# Nusbio_smd.net
KiCad netlist of a schematic drawn in EAGLE
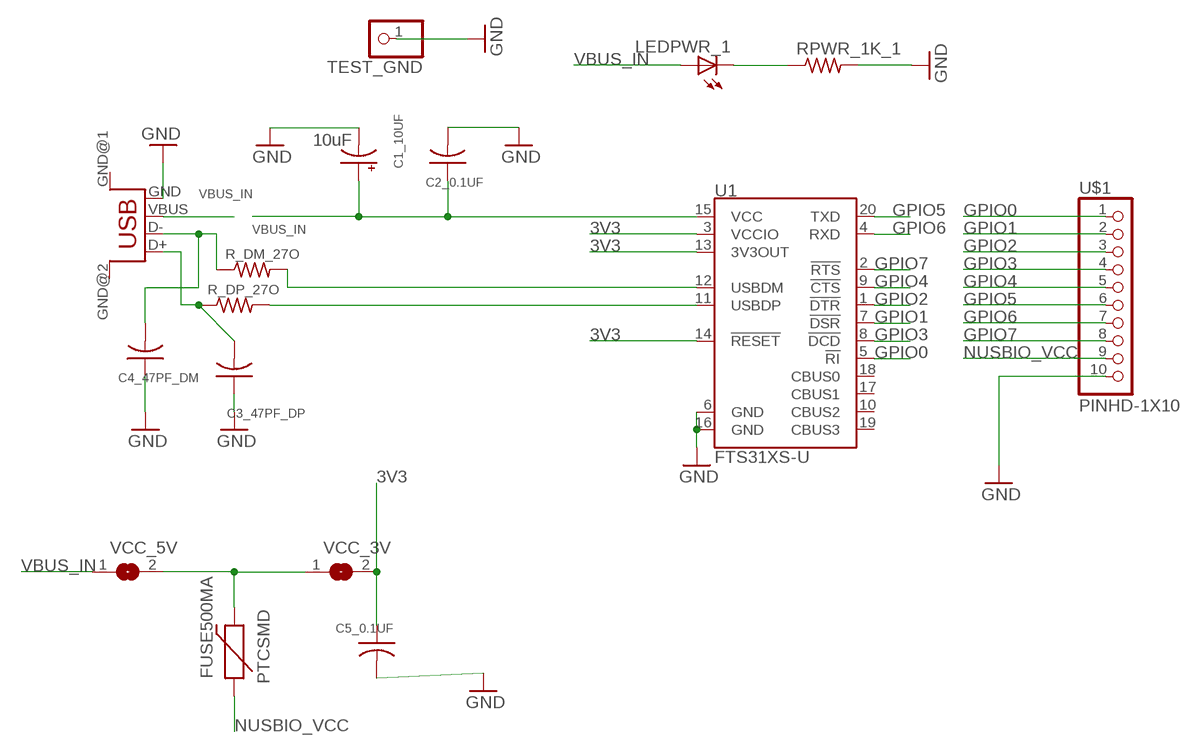
[diagram p0: schematic, sheet 1]

(export (version "E")
  (design (tool "Eeschema 10.0.6"))
  (components
    (comp (ref "C1_10UF")
      (value "10uF")
      (footprint "eagle-import:EIA3216")
      (libsource (lib "eagle-import") (part "10UF-16V-10%(TANT)"))
    )
    (comp (ref "C2_0.1UF")
      (value "C-USC1206")
      (footprint "eagle-import:C1206")
      (libsource (lib "eagle-import") (part "C-USC1206"))
    )
    (comp (ref "C3_47PF_DP")
      (value "C-USC1206")
      (footprint "eagle-import:C1206")
      (libsource (lib "eagle-import") (part "C-USC1206"))
    )
    (comp (ref "C4_47PF_DM")
      (value "C-USC1206")
      (footprint "eagle-import:C1206")
      (libsource (lib "eagle-import") (part "C-USC1206"))
    )
    (comp (ref "C5_0.1UF")
      (value "C-USC1206")
      (footprint "eagle-import:C1206")
      (libsource (lib "eagle-import") (part "C-USC1206"))
    )
    (comp (ref "FUSE500MA")
      (value "PTCSMD")
      (footprint "eagle-import:PTC-1206")
      (libsource (lib "eagle-import") (part "PTCSMD"))
    )
    (comp (ref "LEDPWR_1")
      (value "LEDCHIPLED_0805")
      (footprint "eagle-import:CHIPLED_0805")
      (libsource (lib "eagle-import") (part "LEDCHIPLED_0805"))
    )
    (comp (ref "RPWR_1K_1")
      (value "R-US_R0805")
      (footprint "eagle-import:R0805")
      (libsource (lib "eagle-import") (part "R-US_R0805"))
    )
    (comp (ref "R_DM_27O")
      (value "R-US_R0805")
      (footprint "eagle-import:R0805")
      (libsource (lib "eagle-import") (part "R-US_R0805"))
    )
    (comp (ref "R_DP_27O")
      (value "R-US_R0805")
      (footprint "eagle-import:R0805")
      (libsource (lib "eagle-import") (part "R-US_R0805"))
    )
    (comp (ref "TEST_GND")
      (value "PINHD-1X1")
      (footprint "eagle-import:1X01")
      (libsource (lib "eagle-import") (part "PINHD-1X1"))
    )
    (comp (ref "U$1")
      (value "PINHD-1X10")
      (footprint "eagle-import:1X10-BIG")
      (libsource (lib "eagle-import") (part "PINHD-1X10"))
    )
    (comp (ref "U1")
      (value "FTS31XS-U")
      (footprint "eagle-import:SSOP20_L")
      (libsource (lib "eagle-import") (part "FT231XS"))
    )
    (comp (ref "USB_FEMALE")
      (value "USB")
      (footprint "eagle-import:USB-FEMALE-A-PTH")
      (libsource (lib "eagle-import") (part "USB"))
    )
    (comp (ref "VCC_3V")
      (value "SOLDERJUMPERREFLOW")
      (footprint "eagle-import:SOLDERJUMPER_REFLOW")
      (libsource (lib "eagle-import") (part "SOLDERJUMPERREFLOW"))
    )
    (comp (ref "VCC_5V")
      (value "SOLDERJUMPERREFLOW")
      (footprint "eagle-import:SOLDERJUMPER_REFLOW")
      (libsource (lib "eagle-import") (part "SOLDERJUMPERREFLOW"))
    )
  )
  (nets
    (net (code "1") (name "/3V3") (class "Default")
      (node (ref "C5_0.1UF") (pin "1") (pinfunction "1_1") (pintype "passive"))
      (node (ref "U1") (pin "13") (pinfunction "3V3OUT_13") (pintype "bidirectional"))
      (node (ref "U1") (pin "14") (pinfunction "~{RESET}_14") (pintype "bidirectional"))
      (node (ref "U1") (pin "3") (pinfunction "VCCIO_3") (pintype "bidirectional"))
      (node (ref "VCC_3V") (pin "2") (pinfunction "2_2") (pintype "passive"))
    )
    (net (code "2") (name "/GPIO0") (class "Default")
      (node (ref "U$1") (pin "1") (pinfunction "1_1") (pintype "passive"))
      (node (ref "U1") (pin "5") (pinfunction "~{RI}_5") (pintype "bidirectional"))
    )
    (net (code "3") (name "/GPIO1") (class "Default")
      (node (ref "U$1") (pin "2") (pinfunction "2_2") (pintype "passive"))
      (node (ref "U1") (pin "7") (pinfunction "~{DSR}_7") (pintype "bidirectional"))
    )
    (net (code "4") (name "/GPIO2") (class "Default")
      (node (ref "U$1") (pin "3") (pinfunction "3_3") (pintype "passive"))
      (node (ref "U1") (pin "1") (pinfunction "~{DTR}_1") (pintype "bidirectional"))
    )
    (net (code "5") (name "/GPIO3") (class "Default")
      (node (ref "U$1") (pin "4") (pinfunction "4_4") (pintype "passive"))
      (node (ref "U1") (pin "8") (pinfunction "~{DCD}_8") (pintype "bidirectional"))
    )
    (net (code "6") (name "/GPIO4") (class "Default")
      (node (ref "U$1") (pin "5") (pinfunction "5_5") (pintype "passive"))
      (node (ref "U1") (pin "9") (pinfunction "~{CTS}_9") (pintype "bidirectional"))
    )
    (net (code "7") (name "/GPIO5") (class "Default")
      (node (ref "U$1") (pin "6") (pinfunction "6_6") (pintype "passive"))
      (node (ref "U1") (pin "20") (pinfunction "TXD_20") (pintype "bidirectional"))
    )
    (net (code "8") (name "/GPIO6") (class "Default")
      (node (ref "U$1") (pin "7") (pinfunction "7_7") (pintype "passive"))
      (node (ref "U1") (pin "4") (pinfunction "RXD_4") (pintype "bidirectional"))
    )
    (net (code "9") (name "/GPIO7") (class "Default")
      (node (ref "U$1") (pin "8") (pinfunction "8_8") (pintype "passive"))
      (node (ref "U1") (pin "2") (pinfunction "~{RTS}_2") (pintype "bidirectional"))
    )
    (net (code "10") (name "/NUSBIO_VCC") (class "Default")
      (node (ref "FUSE500MA") (pin "1") (pinfunction "1_1") (pintype "bidirectional"))
      (node (ref "U$1") (pin "9") (pinfunction "9_9") (pintype "passive"))
    )
    (net (code "11") (name "/VBUS_IN") (class "Default")
      (node (ref "C1_10UF") (pin "A") (pinfunction "+_A") (pintype "passive"))
      (node (ref "C2_0.1UF") (pin "1") (pinfunction "1_1") (pintype "passive"))
      (node (ref "LEDPWR_1") (pin "A") (pinfunction "A_A") (pintype "passive"))
      (node (ref "U1") (pin "15") (pinfunction "VCC_15") (pintype "bidirectional"))
      (node (ref "USB_FEMALE") (pin "VBUS") (pinfunction "VBUS_VBUS") (pintype "bidirectional"))
      (node (ref "VCC_5V") (pin "1") (pinfunction "1_1") (pintype "passive"))
    )
    (net (code "12") (name "GND") (class "Default")
      (node (ref "C1_10UF") (pin "C") (pinfunction "-_C") (pintype "passive"))
      (node (ref "C2_0.1UF") (pin "2") (pinfunction "2_2") (pintype "passive"))
      (node (ref "C3_47PF_DP") (pin "1") (pinfunction "1_1") (pintype "passive"))
      (node (ref "C4_47PF_DM") (pin "1") (pinfunction "1_1") (pintype "passive"))
      (node (ref "C5_0.1UF") (pin "2") (pinfunction "2_2") (pintype "passive"))
      (node (ref "RPWR_1K_1") (pin "2") (pinfunction "2_2") (pintype "passive"))
      (node (ref "TEST_GND") (pin "1") (pinfunction "1_1") (pintype "passive"))
      (node (ref "U$1") (pin "10") (pinfunction "10_10") (pintype "passive"))
      (node (ref "U1") (pin "16") (pinfunction "GND_16") (pintype "bidirectional"))
      (node (ref "U1") (pin "6") (pinfunction "GND_6") (pintype "bidirectional"))
      (node (ref "USB_FEMALE") (pin "GND") (pinfunction "GND_GND") (pintype "bidirectional"))
    )
    (net (code "13") (name "Net-(C3_47PF_DP-Pad2)") (class "Default")
      (node (ref "C3_47PF_DP") (pin "2") (pinfunction "2_2") (pintype "passive"))
      (node (ref "R_DP_27O") (pin "1") (pinfunction "1_1") (pintype "passive"))
      (node (ref "USB_FEMALE") (pin "D+") (pinfunction "D+_D+") (pintype "bidirectional"))
    )
    (net (code "14") (name "Net-(C4_47PF_DM-Pad2)") (class "Default")
      (node (ref "C4_47PF_DM") (pin "2") (pinfunction "2_2") (pintype "passive"))
      (node (ref "R_DM_27O") (pin "1") (pinfunction "1_1") (pintype "passive"))
      (node (ref "USB_FEMALE") (pin "D-") (pinfunction "D-_D-") (pintype "bidirectional"))
    )
    (net (code "15") (name "Net-(FUSE500MA-Pad2)") (class "Default")
      (node (ref "FUSE500MA") (pin "2") (pinfunction "2_2") (pintype "bidirectional"))
      (node (ref "VCC_3V") (pin "1") (pinfunction "1_1") (pintype "passive"))
      (node (ref "VCC_5V") (pin "2") (pinfunction "2_2") (pintype "passive"))
    )
    (net (code "16") (name "Net-(LEDPWR_1-PadC)") (class "Default")
      (node (ref "LEDPWR_1") (pin "C") (pinfunction "C_C") (pintype "passive"))
      (node (ref "RPWR_1K_1") (pin "1") (pinfunction "1_1") (pintype "passive"))
    )
    (net (code "17") (name "Net-(U1-USBDM)") (class "Default")
      (node (ref "R_DM_27O") (pin "2") (pinfunction "2_2") (pintype "passive"))
      (node (ref "U1") (pin "12") (pinfunction "USBDM_12") (pintype "bidirectional"))
    )
    (net (code "18") (name "Net-(U1-USBDP)") (class "Default")
      (node (ref "R_DP_27O") (pin "2") (pinfunction "2_2") (pintype "passive"))
      (node (ref "U1") (pin "11") (pinfunction "USBDP_11") (pintype "bidirectional"))
    )
    (net (code "19") (name "unconnected-(U1-CBUS0-Pad18)") (class "Default")
      (node (ref "U1") (pin "18") (pinfunction "CBUS0_18") (pintype "bidirectional"))
    )
    (net (code "20") (name "unconnected-(U1-CBUS1-Pad17)") (class "Default")
      (node (ref "U1") (pin "17") (pinfunction "CBUS1_17") (pintype "bidirectional"))
    )
    (net (code "21") (name "unconnected-(U1-CBUS2-Pad10)") (class "Default")
      (node (ref "U1") (pin "10") (pinfunction "CBUS2_10") (pintype "bidirectional"))
    )
    (net (code "22") (name "unconnected-(U1-CBUS3-Pad19)") (class "Default")
      (node (ref "U1") (pin "19") (pinfunction "CBUS3_19") (pintype "bidirectional"))
    )
    (net (code "23") (name "unconnected-(USB_FEMALE-GND-PadGND@1)") (class "Default")
      (node (ref "USB_FEMALE") (pin "GND@1") (pinfunction "GND_GND@1") (pintype "bidirectional"))
    )
    (net (code "24") (name "unconnected-(USB_FEMALE-GND-PadGND@2)") (class "Default")
      (node (ref "USB_FEMALE") (pin "GND@2") (pinfunction "GND_GND@2") (pintype "bidirectional"))
    )
  )
)
